# MPP_M2_extension.net
KiCad netlist of a schematic drawn in Altium Designer
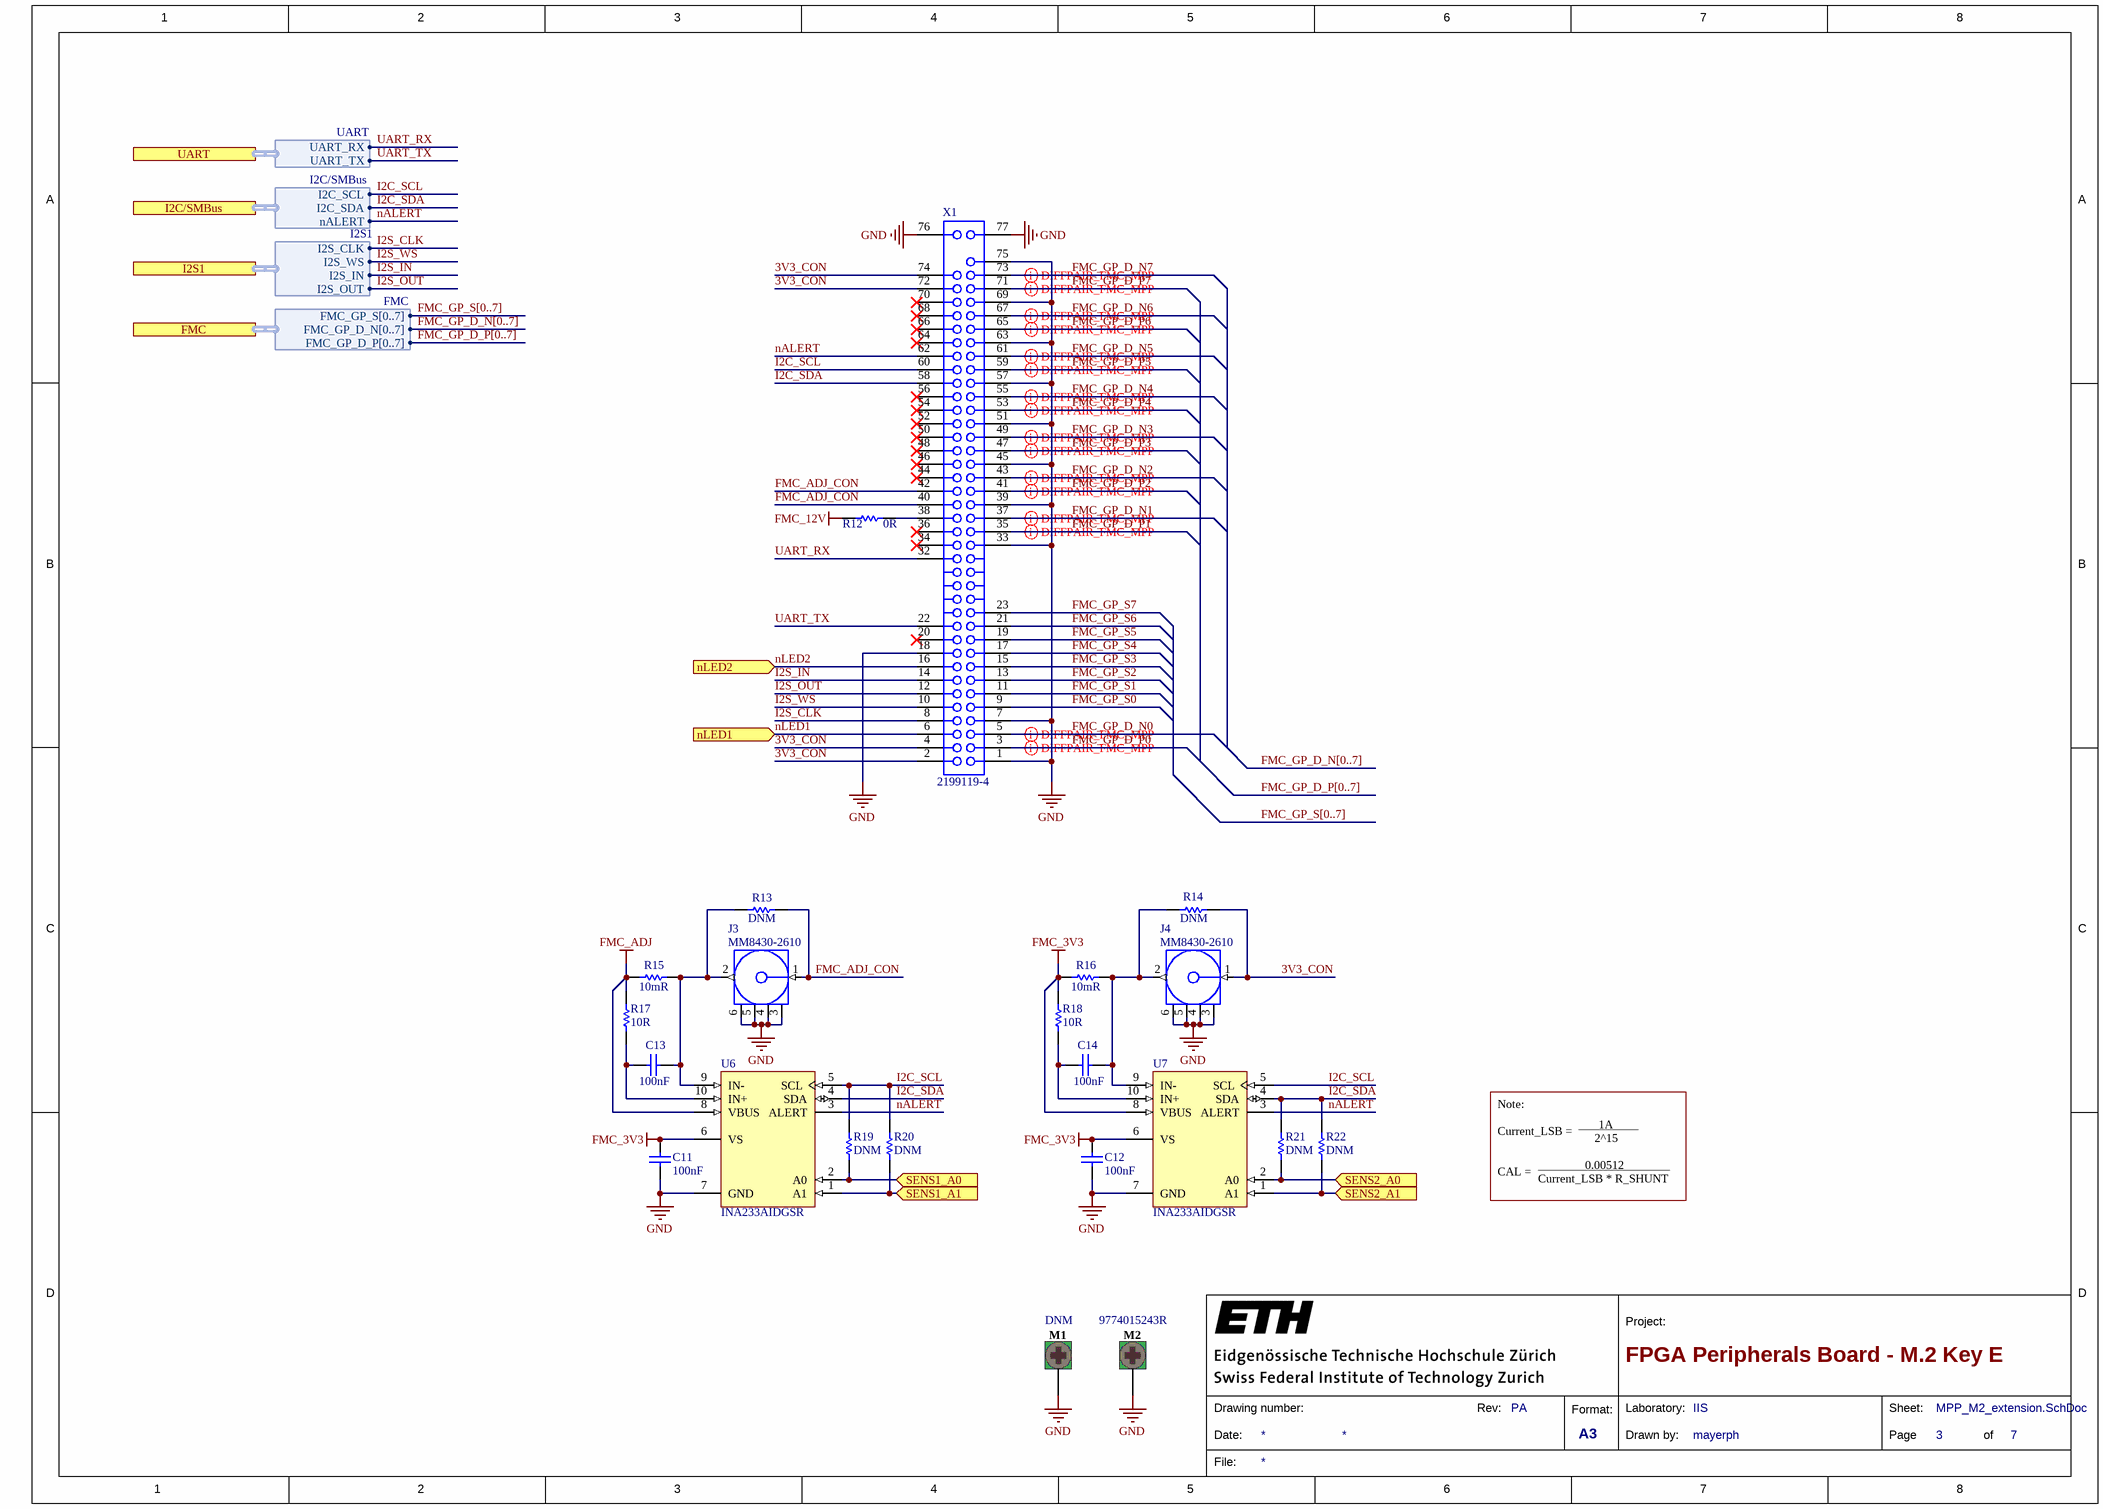
[diagram p0: MPP_M2_extension.SchDoc]

(export (version "E")
  (design (tool "Eeschema 10.0.6"))
  (components
    (comp (ref "C11")
      (value "100nF")
      (footprint "CAPC1050X55X23LL05T13")
      (description "Chip Capacitor, 100 nF, +/- 10%, 16 V, -55 to 125 degC, 0402 (1005 Metric), RoHS, Tape and Reel")
      (fields
        (field (name "MANUFACTURER") "Samsung Electro-Mechanics")
        (field (name "MANUFACTURER PART NUMBER") "CL05B104KO5NNNC")
      )
      (libsource (lib "Altium Content Vault") (part "CAP-NP-2"))
    )
    (comp (ref "C12")
      (value "100nF")
      (footprint "CAPC1050X55X23LL05T13")
      (description "Chip Capacitor, 100 nF, +/- 10%, 16 V, -55 to 125 degC, 0402 (1005 Metric), RoHS, Tape and Reel")
      (fields
        (field (name "MANUFACTURER") "Samsung Electro-Mechanics")
        (field (name "MANUFACTURER PART NUMBER") "CL05B104KO5NNNC")
      )
      (libsource (lib "Altium Content Vault") (part "CAP-NP-2"))
    )
    (comp (ref "C13")
      (value "100nF")
      (footprint "CAPC1050X55X23LL05T13")
      (description "Chip Capacitor, 100 nF, +/- 10%, 16 V, -55 to 125 degC, 0402 (1005 Metric), RoHS, Tape and Reel")
      (fields
        (field (name "MANUFACTURER") "Samsung Electro-Mechanics")
        (field (name "MANUFACTURER PART NUMBER") "CL05B104KO5NNNC")
      )
      (libsource (lib "Altium Content Vault") (part "CAP-NP-2"))
    )
    (comp (ref "C14")
      (value "100nF")
      (footprint "CAPC1050X55X23LL05T13")
      (description "Chip Capacitor, 100 nF, +/- 10%, 16 V, -55 to 125 degC, 0402 (1005 Metric), RoHS, Tape and Reel")
      (fields
        (field (name "MANUFACTURER") "Samsung Electro-Mechanics")
        (field (name "MANUFACTURER PART NUMBER") "CL05B104KO5NNNC")
      )
      (libsource (lib "Altium Content Vault") (part "CAP-NP-2"))
    )
    (comp (ref "J3")
      (value "MM8430-2610")
      (footprint "MM8430-2610")
      (description "SWD Connector Receptacle, Female Socket 50Ohm Surface Mount Solder")
      (fields
        (field (name "MANUFACTURER") "Murata")
        (field (name "MANUFACTURER PART NUMBER") "MM8430-2610RA1")
      )
      (libsource (lib "ETHZ Vault") (part "CONN RF SWITCH"))
    )
    (comp (ref "J4")
      (value "MM8430-2610")
      (footprint "MM8430-2610")
      (description "SWD Connector Receptacle, Female Socket 50Ohm Surface Mount Solder")
      (fields
        (field (name "MANUFACTURER") "Murata")
        (field (name "MANUFACTURER PART NUMBER") "MM8430-2610RA1")
      )
      (libsource (lib "ETHZ Vault") (part "CONN RF SWITCH"))
    )
    (comp (ref "M1")
      (value "DNM")
      (footprint "9774015243R")
      (description "RND STANDOFF M2X0.4 STEEL 1.5MM")
      (fields
        (field (name "MANUFACTURER") "Wurth Electronics")
        (field (name "MANUFACTURER PART NUMBER") "9774015243R")
      )
      (libsource (lib "ETHZ Vault") (part "Hole"))
    )
    (comp (ref "M2")
      (value "9774015243R")
      (footprint "9774015243R")
      (description "RND STANDOFF M2X0.4 STEEL 1.5MM")
      (fields (field (name "MANUFACTURER") "Wurth Electronics"))
      (libsource (lib "ETHZ Vault") (part "Hole"))
    )
    (comp (ref "R12")
      (value "0R")
      (footprint "RESC1005X40X25LL05T10")
      (fields
        (field (name "MANUFACTURER") "Yageo")
        (field (name "PART NUMBER") "RC0402JR-070RL")
        (field (name "TOLERANCE") "5%")
      )
      (libsource (lib "Altium Content Vault") (part "RES"))
    )
    (comp (ref "R13")
      (value "DNM")
      (footprint "RESC1005X40X25LL05T10")
      (fields
        (field (name "MANUFACTURER") "Yageo")
        (field (name "PART NUMBER") "RC0402JR-070RL")
        (field (name "TOLERANCE") "5%")
      )
      (libsource (lib "Altium Content Vault") (part "RES"))
    )
    (comp (ref "R14")
      (value "DNM")
      (footprint "RESC1005X40X25LL05T10")
      (fields
        (field (name "MANUFACTURER") "Yageo")
        (field (name "PART NUMBER") "RC0402JR-070RL")
        (field (name "TOLERANCE") "5%")
      )
      (libsource (lib "Altium Content Vault") (part "RES"))
    )
    (comp (ref "R15")
      (value "10mR")
      (footprint "RESC3116X65X40NL10T20")
      (fields
        (field (name "PART NUMBER") "RL1206FR-070R01L")
        (field (name "MANUFACTURER") "Yageo")
        (field (name "TOLERANCE") "1%")
      )
      (libsource (lib "Altium Content Vault") (part "RES"))
    )
    (comp (ref "R16")
      (value "10mR")
      (footprint "RESC3116X65X40NL10T20")
      (fields
        (field (name "PART NUMBER") "RL1206FR-070R01L")
        (field (name "MANUFACTURER") "Yageo")
        (field (name "TOLERANCE") "1%")
      )
      (libsource (lib "Altium Content Vault") (part "RES"))
    )
    (comp (ref "R17")
      (value "10R")
      (footprint "RESC1005X40X25LL10T10")
      (fields
        (field (name "MANUFACTURER") "Bourns")
        (field (name "PART NUMBER") "CR0402-FX-10R0GLF")
        (field (name "TOLERANCE") "1%")
      )
      (libsource (lib "Altium Content Vault") (part "RES"))
    )
    (comp (ref "R18")
      (value "10R")
      (footprint "RESC1005X40X25LL10T10")
      (fields
        (field (name "MANUFACTURER") "Bourns")
        (field (name "PART NUMBER") "CR0402-FX-10R0GLF")
        (field (name "TOLERANCE") "1%")
      )
      (libsource (lib "Altium Content Vault") (part "RES"))
    )
    (comp (ref "R19")
      (value "DNM")
      (footprint "RESC1005X40X25LL05T10")
      (fields
        (field (name "MANUFACTURER") "Yageo")
        (field (name "PART NUMBER") "RC0402JR-070RL")
        (field (name "TOLERANCE") "5%")
      )
      (libsource (lib "Altium Content Vault") (part "RES"))
    )
    (comp (ref "R20")
      (value "DNM")
      (footprint "RESC1005X40X25LL05T10")
      (fields
        (field (name "MANUFACTURER") "Yageo")
        (field (name "PART NUMBER") "RC0402JR-070RL")
        (field (name "TOLERANCE") "5%")
      )
      (libsource (lib "Altium Content Vault") (part "RES"))
    )
    (comp (ref "R21")
      (value "DNM")
      (footprint "RESC1005X40X25LL05T10")
      (fields
        (field (name "MANUFACTURER") "Yageo")
        (field (name "PART NUMBER") "RC0402JR-070RL")
        (field (name "TOLERANCE") "5%")
      )
      (libsource (lib "Altium Content Vault") (part "RES"))
    )
    (comp (ref "R22")
      (value "DNM")
      (footprint "RESC1005X40X25LL05T10")
      (fields
        (field (name "MANUFACTURER") "Yageo")
        (field (name "PART NUMBER") "RC0402JR-070RL")
        (field (name "TOLERANCE") "5%")
      )
      (libsource (lib "Altium Content Vault") (part "RES"))
    )
    (comp (ref "U6")
      (value "INA233AIDGSR")
      (footprint "ADI-RM-10_N")
      (description "Current Monitor Regulator High/Low-Side 10mA 10-VSSOP")
      (fields (field (name "MANUFACTURER") "Texas Instruments"))
      (libsource (lib "ETHZ Vault") (part "INA233"))
    )
    (comp (ref "U7")
      (value "INA233AIDGSR")
      (footprint "ADI-RM-10_N")
      (description "Current Monitor Regulator High/Low-Side 10mA 10-VSSOP")
      (fields (field (name "MANUFACTURER") "Texas Instruments"))
      (libsource (lib "ETHZ Vault") (part "INA233"))
    )
    (comp (ref "X1")
      (value "2199119-4")
      (footprint "2199119-4")
      (description "67 Position Female Connector M.2 (NGFF) Mini Card Gold 0.020\" (0.50mm) Black")
      (fields
        (field (name "MANUFACTURER") "TE Connectivity")
        (field (name "MANUFACTURER PART NUMBER") "2199230-4")
      )
      (libsource (lib "ETHZ Vault") (part "2199119-4"))
    )
  )
  (nets
    (net (code "5") (name "/3V3_CON") (class "Default")
      (node (ref "J4") (pin "1") (pinfunction "Signal_1") (pintype "input"))
      (node (ref "R14") (pin "1") (pinfunction "1_1") (pintype "passive"))
      (node (ref "X1") (pin "2") (pinfunction "2_2") (pintype "passive"))
      (node (ref "X1") (pin "4") (pinfunction "4_4") (pintype "passive"))
      (node (ref "X1") (pin "72") (pinfunction "72_72") (pintype "passive"))
      (node (ref "X1") (pin "74") (pinfunction "74_74") (pintype "passive"))
    )
    (net (code "6") (name "/FMC_ADJ_CON") (class "Default")
      (node (ref "J3") (pin "1") (pinfunction "Signal_1") (pintype "input"))
      (node (ref "R13") (pin "1") (pinfunction "1_1") (pintype "passive"))
      (node (ref "X1") (pin "40") (pinfunction "40_40") (pintype "passive"))
      (node (ref "X1") (pin "42") (pinfunction "42_42") (pintype "passive"))
    )
    (net (code "7") (name "/FMC_GP_D_N0") (class "Default")
      (node (ref "X1") (pin "5") (pinfunction "5_5") (pintype "passive"))
    )
    (net (code "8") (name "/FMC_GP_D_N1") (class "Default")
      (node (ref "X1") (pin "37") (pinfunction "37_37") (pintype "passive"))
    )
    (net (code "9") (name "/FMC_GP_D_N2") (class "Default")
      (node (ref "X1") (pin "43") (pinfunction "43_43") (pintype "passive"))
    )
    (net (code "10") (name "/FMC_GP_D_N3") (class "Default")
      (node (ref "X1") (pin "49") (pinfunction "49_49") (pintype "passive"))
    )
    (net (code "11") (name "/FMC_GP_D_N4") (class "Default")
      (node (ref "X1") (pin "55") (pinfunction "55_55") (pintype "passive"))
    )
    (net (code "12") (name "/FMC_GP_D_N5") (class "Default")
      (node (ref "X1") (pin "61") (pinfunction "61_61") (pintype "passive"))
    )
    (net (code "13") (name "/FMC_GP_D_N6") (class "Default")
      (node (ref "X1") (pin "67") (pinfunction "67_67") (pintype "passive"))
    )
    (net (code "14") (name "/FMC_GP_D_N7") (class "Default")
      (node (ref "X1") (pin "73") (pinfunction "73_73") (pintype "passive"))
    )
    (net (code "16") (name "/FMC_GP_D_P0") (class "Default")
      (node (ref "X1") (pin "3") (pinfunction "3_3") (pintype "passive"))
    )
    (net (code "17") (name "/FMC_GP_D_P1") (class "Default")
      (node (ref "X1") (pin "35") (pinfunction "35_35") (pintype "passive"))
    )
    (net (code "18") (name "/FMC_GP_D_P2") (class "Default")
      (node (ref "X1") (pin "41") (pinfunction "41_41") (pintype "passive"))
    )
    (net (code "19") (name "/FMC_GP_D_P3") (class "Default")
      (node (ref "X1") (pin "47") (pinfunction "47_47") (pintype "passive"))
    )
    (net (code "20") (name "/FMC_GP_D_P4") (class "Default")
      (node (ref "X1") (pin "53") (pinfunction "53_53") (pintype "passive"))
    )
    (net (code "21") (name "/FMC_GP_D_P5") (class "Default")
      (node (ref "X1") (pin "59") (pinfunction "59_59") (pintype "passive"))
    )
    (net (code "22") (name "/FMC_GP_D_P6") (class "Default")
      (node (ref "X1") (pin "65") (pinfunction "65_65") (pintype "passive"))
    )
    (net (code "23") (name "/FMC_GP_D_P7") (class "Default")
      (node (ref "X1") (pin "71") (pinfunction "71_71") (pintype "passive"))
    )
    (net (code "25") (name "/FMC_GP_S0") (class "Default")
      (node (ref "X1") (pin "9") (pinfunction "9_9") (pintype "passive"))
    )
    (net (code "26") (name "/FMC_GP_S1") (class "Default")
      (node (ref "X1") (pin "11") (pinfunction "11_11") (pintype "passive"))
    )
    (net (code "27") (name "/FMC_GP_S2") (class "Default")
      (node (ref "X1") (pin "13") (pinfunction "13_13") (pintype "passive"))
    )
    (net (code "28") (name "/FMC_GP_S3") (class "Default")
      (node (ref "X1") (pin "15") (pinfunction "15_15") (pintype "passive"))
    )
    (net (code "29") (name "/FMC_GP_S4") (class "Default")
      (node (ref "X1") (pin "17") (pinfunction "17_17") (pintype "passive"))
    )
    (net (code "30") (name "/FMC_GP_S5") (class "Default")
      (node (ref "X1") (pin "19") (pinfunction "19_19") (pintype "passive"))
    )
    (net (code "31") (name "/FMC_GP_S6") (class "Default")
      (node (ref "X1") (pin "21") (pinfunction "21_21") (pintype "passive"))
    )
    (net (code "32") (name "/FMC_GP_S7") (class "Default")
      (node (ref "X1") (pin "23") (pinfunction "23_23") (pintype "passive"))
    )
    (net (code "34") (name "/I2C_SCL") (class "Default")
      (node (ref "R19") (pin "1") (pinfunction "1_1") (pintype "passive"))
      (node (ref "R20") (pin "1") (pinfunction "1_1") (pintype "passive"))
      (node (ref "U6") (pin "5") (pinfunction "SCL_5") (pintype "input"))
      (node (ref "U7") (pin "5") (pinfunction "SCL_5") (pintype "input"))
      (node (ref "X1") (pin "60") (pinfunction "55_60") (pintype "passive"))
    )
    (net (code "35") (name "/I2C_SDA") (class "Default")
      (node (ref "R21") (pin "1") (pinfunction "1_1") (pintype "passive"))
      (node (ref "R22") (pin "1") (pinfunction "1_1") (pintype "passive"))
      (node (ref "U6") (pin "4") (pinfunction "SDA_4") (pintype "bidirectional"))
      (node (ref "U7") (pin "4") (pinfunction "SDA_4") (pintype "bidirectional"))
      (node (ref "X1") (pin "58") (pinfunction "54_58") (pintype "passive"))
    )
    (net (code "36") (name "/I2S_CLK") (class "Default")
      (node (ref "X1") (pin "8") (pinfunction "8_8") (pintype "passive"))
    )
    (net (code "37") (name "/I2S_IN") (class "Default")
      (node (ref "X1") (pin "14") (pinfunction "14_14") (pintype "passive"))
    )
    (net (code "38") (name "/I2S_OUT") (class "Default")
      (node (ref "X1") (pin "12") (pinfunction "12_12") (pintype "passive"))
    )
    (net (code "39") (name "/I2S_WS") (class "Default")
      (node (ref "X1") (pin "10") (pinfunction "10_10") (pintype "passive"))
    )
    (net (code "40") (name "/SENS1_A0") (class "Default")
      (node (ref "R19") (pin "2") (pinfunction "2_2") (pintype "passive"))
      (node (ref "U6") (pin "2") (pinfunction "A0_2") (pintype "input"))
    )
    (net (code "41") (name "/SENS1_A1") (class "Default")
      (node (ref "R20") (pin "2") (pinfunction "2_2") (pintype "passive"))
      (node (ref "U6") (pin "1") (pinfunction "A1_1") (pintype "input"))
    )
    (net (code "42") (name "/SENS2_A0") (class "Default")
      (node (ref "R21") (pin "2") (pinfunction "2_2") (pintype "passive"))
      (node (ref "U7") (pin "2") (pinfunction "A0_2") (pintype "input"))
    )
    (net (code "43") (name "/SENS2_A1") (class "Default")
      (node (ref "R22") (pin "2") (pinfunction "2_2") (pintype "passive"))
      (node (ref "U7") (pin "1") (pinfunction "A1_1") (pintype "input"))
    )
    (net (code "44") (name "/UART_RX") (class "Default")
      (node (ref "X1") (pin "32") (pinfunction "32_32") (pintype "passive"))
    )
    (net (code "45") (name "/UART_TX") (class "Default")
      (node (ref "X1") (pin "22") (pinfunction "22_22") (pintype "passive"))
    )
    (net (code "46") (name "/nALERT") (class "Default")
      (node (ref "U6") (pin "3") (pinfunction "ALERT_3") (pintype "open_collector"))
      (node (ref "U7") (pin "3") (pinfunction "ALERT_3") (pintype "open_collector"))
      (node (ref "X1") (pin "62") (pinfunction "62_62") (pintype "passive"))
    )
    (net (code "47") (name "/nLED1") (class "Default")
      (node (ref "X1") (pin "6") (pinfunction "6_6") (pintype "passive"))
    )
    (net (code "48") (name "/nLED2") (class "Default")
      (node (ref "X1") (pin "16") (pinfunction "16_16") (pintype "passive"))
    )
    (net (code "53") (name "FMC_3V3") (class "Default")
      (node (ref "C11") (pin "2") (pinfunction "2_2") (pintype "passive"))
      (node (ref "C12") (pin "2") (pinfunction "2_2") (pintype "passive"))
      (node (ref "R16") (pin "1") (pinfunction "1_1") (pintype "passive"))
      (node (ref "R18") (pin "2") (pinfunction "2_2") (pintype "passive"))
      (node (ref "U6") (pin "6") (pinfunction "VS_6") (pintype "power_in"))
      (node (ref "U7") (pin "6") (pinfunction "VS_6") (pintype "power_in"))
      (node (ref "U7") (pin "8") (pinfunction "VBUS_8") (pintype "input"))
    )
    (net (code "54") (name "FMC_12V") (class "Default")
      (node (ref "R12") (pin "2") (pinfunction "2_2") (pintype "passive"))
    )
    (net (code "55") (name "FMC_ADJ") (class "Default")
      (node (ref "R15") (pin "1") (pinfunction "1_1") (pintype "passive"))
      (node (ref "R17") (pin "2") (pinfunction "2_2") (pintype "passive"))
      (node (ref "U6") (pin "8") (pinfunction "VBUS_8") (pintype "input"))
    )
    (net (code "56") (name "GND") (class "Default")
      (node (ref "C11") (pin "1") (pinfunction "1_1") (pintype "passive"))
      (node (ref "C12") (pin "1") (pinfunction "1_1") (pintype "passive"))
      (node (ref "J3") (pin "3") (pinfunction "GND_3") (pintype "power_in"))
      (node (ref "J3") (pin "4") (pinfunction "GND_4") (pintype "power_in"))
      (node (ref "J3") (pin "5") (pinfunction "GND_5") (pintype "power_in"))
      (node (ref "J3") (pin "6") (pinfunction "GND_6") (pintype "power_in"))
      (node (ref "J4") (pin "3") (pinfunction "GND_3") (pintype "power_in"))
      (node (ref "J4") (pin "4") (pinfunction "GND_4") (pintype "power_in"))
      (node (ref "J4") (pin "5") (pinfunction "GND_5") (pintype "power_in"))
      (node (ref "J4") (pin "6") (pinfunction "GND_6") (pintype "power_in"))
      (node (ref "M1") (pin "1") (pinfunction "1_1") (pintype "passive"))
      (node (ref "M2") (pin "1") (pinfunction "1_1") (pintype "passive"))
      (node (ref "U6") (pin "7") (pinfunction "GND_7") (pintype "power_in"))
      (node (ref "U7") (pin "7") (pinfunction "GND_7") (pintype "power_in"))
      (node (ref "X1") (pin "1") (pinfunction "1_1") (pintype "passive"))
      (node (ref "X1") (pin "18") (pinfunction "18_18") (pintype "passive"))
      (node (ref "X1") (pin "33") (pinfunction "33_33") (pintype "passive"))
      (node (ref "X1") (pin "39") (pinfunction "39_39") (pintype "passive"))
      (node (ref "X1") (pin "45") (pinfunction "45_45") (pintype "passive"))
      (node (ref "X1") (pin "51") (pinfunction "51_51") (pintype "passive"))
      (node (ref "X1") (pin "57") (pinfunction "57_57") (pintype "passive"))
      (node (ref "X1") (pin "63") (pinfunction "63_63") (pintype "passive"))
      (node (ref "X1") (pin "69") (pinfunction "69_69") (pintype "passive"))
      (node (ref "X1") (pin "7") (pinfunction "7_7") (pintype "passive"))
      (node (ref "X1") (pin "75") (pinfunction "75_75") (pintype "passive"))
      (node (ref "X1") (pin "76") (pinfunction "76_76") (pintype "passive"))
      (node (ref "X1") (pin "77") (pinfunction "77_77") (pintype "passive"))
    )
    (net (code "57") (name "Net-(R12-Pad1)") (class "Default")
      (node (ref "R12") (pin "1") (pinfunction "1_1") (pintype "passive"))
      (node (ref "X1") (pin "38") (pinfunction "38_38") (pintype "passive"))
    )
    (net (code "58") (name "Net-(U6-IN+)") (class "Default")
      (node (ref "C13") (pin "2") (pinfunction "2_2") (pintype "passive"))
      (node (ref "R17") (pin "1") (pinfunction "1_1") (pintype "passive"))
      (node (ref "U6") (pin "10") (pinfunction "IN+_10") (pintype "input"))
    )
    (net (code "59") (name "Net-(U6-IN-)") (class "Default")
      (node (ref "C13") (pin "1") (pinfunction "1_1") (pintype "passive"))
      (node (ref "J3") (pin "2") (pinfunction "Signal_2") (pintype "output"))
      (node (ref "R13") (pin "2") (pinfunction "2_2") (pintype "passive"))
      (node (ref "R15") (pin "2") (pinfunction "2_2") (pintype "passive"))
      (node (ref "U6") (pin "9") (pinfunction "IN-_9") (pintype "input"))
    )
    (net (code "60") (name "Net-(U7-IN+)") (class "Default")
      (node (ref "C14") (pin "2") (pinfunction "2_2") (pintype "passive"))
      (node (ref "R18") (pin "1") (pinfunction "1_1") (pintype "passive"))
      (node (ref "U7") (pin "10") (pinfunction "IN+_10") (pintype "input"))
    )
    (net (code "61") (name "Net-(U7-IN-)") (class "Default")
      (node (ref "C14") (pin "1") (pinfunction "1_1") (pintype "passive"))
      (node (ref "J4") (pin "2") (pinfunction "Signal_2") (pintype "output"))
      (node (ref "R14") (pin "2") (pinfunction "2_2") (pintype "passive"))
      (node (ref "R16") (pin "2") (pinfunction "2_2") (pintype "passive"))
      (node (ref "U7") (pin "9") (pinfunction "IN-_9") (pintype "input"))
    )
    (net (code "62") (name "unconnected-(X1-51-Pad52)") (class "Default")
      (node (ref "X1") (pin "52") (pinfunction "51_52") (pintype "passive+no_connect"))
    )
    (net (code "63") (name "unconnected-(X1-52-Pad54)") (class "Default")
      (node (ref "X1") (pin "54") (pinfunction "52_54") (pintype "passive+no_connect"))
    )
    (net (code "64") (name "unconnected-(X1-53-Pad56)") (class "Default")
      (node (ref "X1") (pin "56") (pinfunction "53_56") (pintype "passive+no_connect"))
    )
    (net (code "65") (name "unconnected-(X1-Pad20)") (class "Default")
      (node (ref "X1") (pin "20") (pinfunction "20_20") (pintype "passive+no_connect"))
    )
    (net (code "66") (name "unconnected-(X1-Pad34)") (class "Default")
      (node (ref "X1") (pin "34") (pinfunction "34_34") (pintype "passive+no_connect"))
    )
    (net (code "67") (name "unconnected-(X1-Pad36)") (class "Default")
      (node (ref "X1") (pin "36") (pinfunction "36_36") (pintype "passive+no_connect"))
    )
    (net (code "68") (name "unconnected-(X1-Pad44)") (class "Default")
      (node (ref "X1") (pin "44") (pinfunction "44_44") (pintype "passive+no_connect"))
    )
    (net (code "69") (name "unconnected-(X1-Pad46)") (class "Default")
      (node (ref "X1") (pin "46") (pinfunction "46_46") (pintype "passive+no_connect"))
    )
    (net (code "70") (name "unconnected-(X1-Pad48)") (class "Default")
      (node (ref "X1") (pin "48") (pinfunction "48_48") (pintype "passive+no_connect"))
    )
    (net (code "71") (name "unconnected-(X1-Pad50)") (class "Default")
      (node (ref "X1") (pin "50") (pinfunction "50_50") (pintype "passive+no_connect"))
    )
    (net (code "72") (name "unconnected-(X1-Pad64)") (class "Default")
      (node (ref "X1") (pin "64") (pinfunction "64_64") (pintype "passive+no_connect"))
    )
    (net (code "73") (name "unconnected-(X1-Pad66)") (class "Default")
      (node (ref "X1") (pin "66") (pinfunction "66_66") (pintype "passive+no_connect"))
    )
    (net (code "74") (name "unconnected-(X1-Pad68)") (class "Default")
      (node (ref "X1") (pin "68") (pinfunction "68_68") (pintype "passive+no_connect"))
    )
    (net (code "75") (name "unconnected-(X1-Pad70)") (class "Default")
      (node (ref "X1") (pin "70") (pinfunction "70_70") (pintype "passive+no_connect"))
    )
  )
)
